# BLE_Reader.net
KiCad netlist of a schematic drawn in Altium Designer
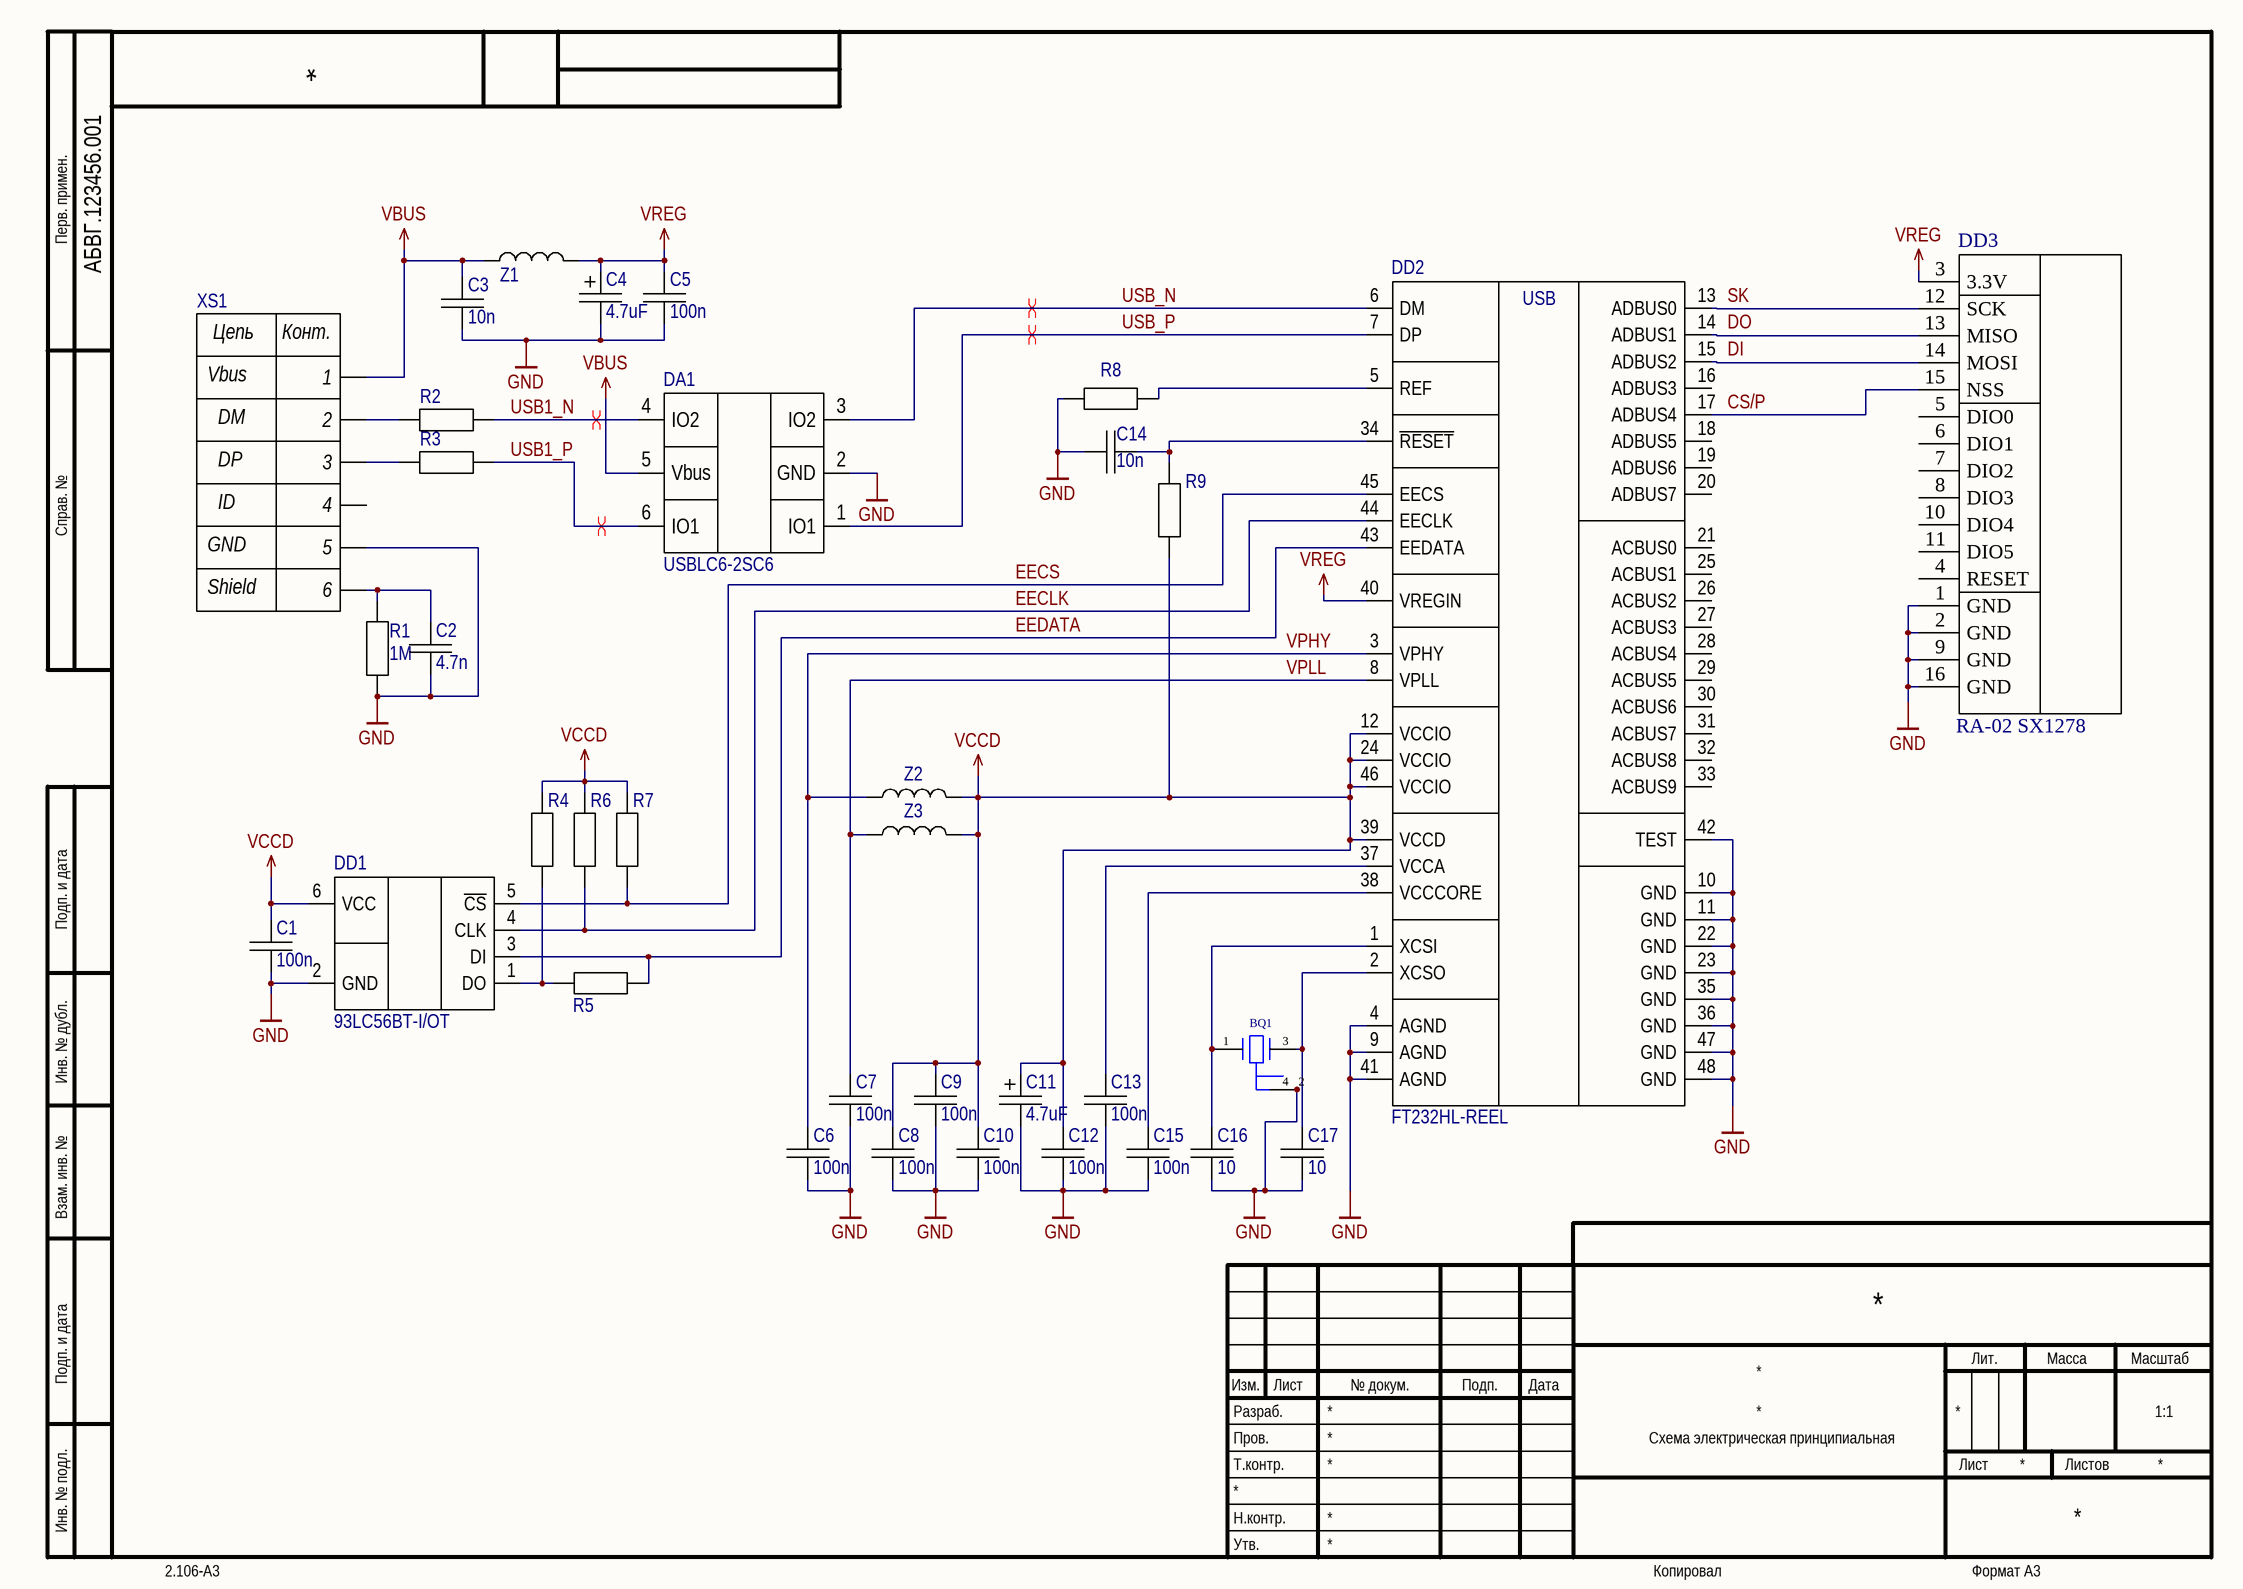
[diagram p0: BLE Reader.SchDoc]

(export (version "E")
  (design (tool "Eeschema 10.0.6"))
  (components
    (comp (ref "BQ1")
      (value "ABM8G-12.000MHZ-4Y-T3")
      (footprint "Abracon_ABM8G_0")
      (libsource (lib "Crys_Abracon_ABM8G-12.000MHZ-4Y-T3_eec") (part "ABM8G-12.000MHZ-4Y-T3"))
    )
    (comp (ref "C1")
      (value "100n")
      (footprint "1608[0603]")
      (description "Конденсатор 1.6x0.8 мм")
      (fields (field (name "TOLERANCE") "±10%"))
      (libsource (lib "RPSLib") (part "CC1608"))
    )
    (comp (ref "C2")
      (value "4.7n")
      (footprint "1608[0603]")
      (description "Конденсатор 1.6x0.8 мм")
      (fields (field (name "TOLERANCE") "±10%"))
      (libsource (lib "RPSLib") (part "CC1608"))
    )
    (comp (ref "C3")
      (value "10n")
      (footprint "1608[0603]")
      (description "Конденсатор 1.6x0.8 мм")
      (fields (field (name "TOLERANCE") "±10%"))
      (libsource (lib "RPSLib") (part "CC1608"))
    )
    (comp (ref "C4")
      (value "4.7uF")
      (footprint "C1206")
      (description "Tantalum Surface Mount Capacitor, Size A")
      (fields (field (name "VOLTAGE") "16"))
      (libsource (lib "RPSLib") (part "CT3216-A"))
    )
    (comp (ref "C5")
      (value "100n")
      (footprint "1608[0603]")
      (description "Конденсатор 1.6x0.8 мм")
      (fields (field (name "TOLERANCE") "±10%"))
      (libsource (lib "RPSLib") (part "CC1608"))
    )
    (comp (ref "C6")
      (value "100n")
      (footprint "1608[0603]")
      (description "Конденсатор 1.6x0.8 мм")
      (fields (field (name "TOLERANCE") "±10%"))
      (libsource (lib "RPSLib") (part "CC1608"))
    )
    (comp (ref "C7")
      (value "100n")
      (footprint "1608[0603]")
      (description "Конденсатор 1.6x0.8 мм")
      (fields (field (name "TOLERANCE") "±10%"))
      (libsource (lib "RPSLib") (part "CC1608"))
    )
    (comp (ref "C8")
      (value "100n")
      (footprint "1608[0603]")
      (description "Конденсатор 1.6x0.8 мм")
      (fields (field (name "TOLERANCE") "±10%"))
      (libsource (lib "RPSLib") (part "CC1608"))
    )
    (comp (ref "C9")
      (value "100n")
      (footprint "1608[0603]")
      (description "Конденсатор 1.6x0.8 мм")
      (fields (field (name "TOLERANCE") "±10%"))
      (libsource (lib "RPSLib") (part "CC1608"))
    )
    (comp (ref "C10")
      (value "100n")
      (footprint "1608[0603]")
      (description "Конденсатор 1.6x0.8 мм")
      (fields (field (name "TOLERANCE") "±10%"))
      (libsource (lib "RPSLib") (part "CC1608"))
    )
    (comp (ref "C11")
      (value "4.7uF")
      (footprint "C1206")
      (description "Tantalum Surface Mount Capacitor, Size A")
      (fields (field (name "VOLTAGE") "16"))
      (libsource (lib "RPSLib") (part "CT3216-A"))
    )
    (comp (ref "C12")
      (value "100n")
      (footprint "1608[0603]")
      (description "Конденсатор 1.6x0.8 мм")
      (fields (field (name "TOLERANCE") "±10%"))
      (libsource (lib "RPSLib") (part "CC1608"))
    )
    (comp (ref "C13")
      (value "100n")
      (footprint "1608[0603]")
      (description "Конденсатор 1.6x0.8 мм")
      (fields (field (name "TOLERANCE") "±10%"))
      (libsource (lib "RPSLib") (part "CC1608"))
    )
    (comp (ref "C14")
      (value "10n")
      (footprint "1608[0603]")
      (description "Конденсатор 1.6x0.8 мм")
      (fields (field (name "TOLERANCE") "±10%"))
      (libsource (lib "RPSLib") (part "CC1608"))
    )
    (comp (ref "C15")
      (value "100n")
      (footprint "1608[0603]")
      (description "Конденсатор 1.6x0.8 мм")
      (fields (field (name "TOLERANCE") "±10%"))
      (libsource (lib "RPSLib") (part "CC1608"))
    )
    (comp (ref "C16")
      (value "10")
      (footprint "1608[0603]")
      (description "Конденсатор 1.6x0.8 мм")
      (fields (field (name "TOLERANCE") "±10%"))
      (libsource (lib "RPSLib") (part "CC1608"))
    )
    (comp (ref "C17")
      (value "10")
      (footprint "1608[0603]")
      (description "Конденсатор 1.6x0.8 мм")
      (fields (field (name "TOLERANCE") "±10%"))
      (libsource (lib "RPSLib") (part "CC1608"))
    )
    (comp (ref "DA1")
      (value "USBLC6-2SC6")
      (footprint "STMicroelectronics_USBLC6-2SC6_0")
      (description "USB protection IC")
      (fields (field (name "MANUFACTURER") "STMicroelectronics"))
      (libsource (lib "RPSLib") (part "USBLC6-2SC6"))
    )
    (comp (ref "DD1")
      (value "93LC56BT-I/OT")
      (footprint "SOT-23-OT6_N")
      (description "IC EEPROM 2K SPI 2MHZ SOT23-6")
      (fields (field (name "MANUFACTURER") "Microchip"))
      (libsource (lib "RPSLib") (part "93LC56BT-I/OT"))
    )
    (comp (ref "DD2")
      (value "FT232HL-REEL")
      (footprint "LQFP-48_L")
      (description "IC HS USB TO UART/FIFO 48LQFP")
      (fields (field (name "MANUFACTURER") "FTDI"))
      (libsource (lib "RPSLib") (part "FT232HL-REEL"))
    )
    (comp (ref "DD3") (value "RA-02 SX1278") (footprint "RA-02") (libsource (lib "RA-02") (part "RA-02")))
    (comp (ref "R1")
      (value "1M")
      (footprint "J1-0603")
      (description "Резистор 1.6x0.8 мм")
      (fields (field (name "TOLERANCE") "±5%") (field (name "MANUFACTURER PART NUMBER") "RC0603JR-071ML"))
      (libsource (lib "RPSLib") (part "R1608"))
    )
    (comp (ref "R2")
      (value "R1608")
      (footprint "J1-0603")
      (description "Резистор 1.6x0.8 мм")
      (fields (field (name "TOLERANCE") "±1%"))
      (libsource (lib "RPSLib") (part "R1608"))
    )
    (comp (ref "R3")
      (value "R1608")
      (footprint "J1-0603")
      (description "Резистор 1.6x0.8 мм")
      (fields (field (name "TOLERANCE") "±1%"))
      (libsource (lib "RPSLib") (part "R1608"))
    )
    (comp (ref "R4")
      (value "R1608")
      (footprint "J1-0603")
      (description "Резистор 1.6x0.8 мм")
      (fields (field (name "TOLERANCE") "±5%"))
      (libsource (lib "RPSLib") (part "R1608"))
    )
    (comp (ref "R5")
      (value "R1608")
      (footprint "J1-0603")
      (description "Резистор 1.6x0.8 мм")
      (fields (field (name "TOLERANCE") "±5%"))
      (libsource (lib "RPSLib") (part "R1608"))
    )
    (comp (ref "R6")
      (value "R1608")
      (footprint "J1-0603")
      (description "Резистор 1.6x0.8 мм")
      (fields (field (name "TOLERANCE") "±5%"))
      (libsource (lib "RPSLib") (part "R1608"))
    )
    (comp (ref "R7")
      (value "R1608")
      (footprint "J1-0603")
      (description "Резистор 1.6x0.8 мм")
      (fields (field (name "TOLERANCE") "±5%"))
      (libsource (lib "RPSLib") (part "R1608"))
    )
    (comp (ref "R8")
      (value "R1608")
      (footprint "J1-0603")
      (description "Резистор 1.6x0.8 мм")
      (fields (field (name "TOLERANCE") "±1%"))
      (libsource (lib "RPSLib") (part "R1608"))
    )
    (comp (ref "R9")
      (value "R1608")
      (footprint "J1-0603")
      (description "Резистор 1.6x0.8 мм")
      (fields (field (name "TOLERANCE") "±5%"))
      (libsource (lib "RPSLib") (part "R1608"))
    )
    (comp (ref "XS1")
      (value "UX60SC-MB-5S8(80)")
      (footprint "UX60SC-MB-5S8(80)")
      (description "USB - mini B USB 2.0 Receptacle Connector 5 Position Surface Mount, Right Angle; Through Hole")
      (fields (field (name "MANUFACTURER") "Hirose"))
      (libsource (lib "RPSLib") (part "UX60SC-MB-5S8(80)"))
    )
    (comp (ref "Z1")
      (value "BLM18AG601SN1D")
      (footprint "INDC1608L")
      (description "FERRITE CHIP 600 OHM 500MA 0603")
      (fields (field (name "MANUFACTURER") "Murata") (field (name "TOLERANCE") "25%"))
      (libsource (lib "RPSLib") (part "BLM18AG601SN1D"))
    )
    (comp (ref "Z2")
      (value "BLM18AG601SN1D")
      (footprint "INDC1608L")
      (description "FERRITE CHIP 600 OHM 500MA 0603")
      (fields (field (name "MANUFACTURER") "Murata") (field (name "TOLERANCE") "25%"))
      (libsource (lib "RPSLib") (part "BLM18AG601SN1D"))
    )
    (comp (ref "Z3")
      (value "BLM18AG601SN1D")
      (footprint "INDC1608L")
      (description "FERRITE CHIP 600 OHM 500MA 0603")
      (fields (field (name "MANUFACTURER") "Murata") (field (name "TOLERANCE") "25%"))
      (libsource (lib "RPSLib") (part "BLM18AG601SN1D"))
    )
  )
  (nets
    (net (code "1") (name "/CS{slash}P") (class "Default")
      (node (ref "DD2") (pin "17") (pinfunction "ADBUS4_17") (pintype "passive"))
      (node (ref "DD3") (pin "15") (pinfunction "NSS_15") (pintype "passive"))
    )
    (net (code "4") (name "/EECLK") (class "Default")
      (node (ref "DD1") (pin "4") (pinfunction "CLK_4") (pintype "passive"))
      (node (ref "DD2") (pin "44") (pinfunction "EECLK_44") (pintype "passive"))
      (node (ref "R6") (pin "1") (pinfunction "1_1") (pintype "passive"))
    )
    (net (code "5") (name "/EECS") (class "Default")
      (node (ref "DD1") (pin "5") (pinfunction "~{CS}_5") (pintype "passive"))
      (node (ref "DD2") (pin "45") (pinfunction "EECS_45") (pintype "passive"))
      (node (ref "R7") (pin "1") (pinfunction "1_1") (pintype "passive"))
    )
    (net (code "6") (name "/EEDATA") (class "Default")
      (node (ref "DD1") (pin "3") (pinfunction "DI_3") (pintype "passive"))
      (node (ref "DD2") (pin "43") (pinfunction "EEDATA_43") (pintype "passive"))
      (node (ref "R5") (pin "1") (pinfunction "1_1") (pintype "passive"))
    )
    (net (code "8") (name "/SK") (class "Default")
      (node (ref "DD2") (pin "13") (pinfunction "ADBUS0_13") (pintype "passive"))
      (node (ref "DD3") (pin "12") (pinfunction "SCK_12") (pintype "passive"))
    )
    (net (code "9") (name "/USB1_N") (class "Default")
      (node (ref "DA1") (pin "4") (pinfunction "IO2_4") (pintype "passive"))
      (node (ref "R2") (pin "1") (pinfunction "1_1") (pintype "passive"))
    )
    (net (code "10") (name "/USB1_P") (class "Default")
      (node (ref "DA1") (pin "6") (pinfunction "IO1_6") (pintype "passive"))
      (node (ref "R3") (pin "1") (pinfunction "1_1") (pintype "passive"))
    )
    (net (code "11") (name "/USB_N") (class "Default")
      (node (ref "DA1") (pin "3") (pinfunction "IO2_3") (pintype "passive"))
      (node (ref "DD2") (pin "6") (pinfunction "DM_6") (pintype "passive"))
    )
    (net (code "12") (name "/USB_P") (class "Default")
      (node (ref "DA1") (pin "1") (pinfunction "IO1_1") (pintype "passive"))
      (node (ref "DD2") (pin "7") (pinfunction "DP_7") (pintype "passive"))
    )
    (net (code "13") (name "/VPHY") (class "Default")
      (node (ref "C6") (pin "2") (pinfunction "2_2") (pintype "passive"))
      (node (ref "DD2") (pin "3") (pinfunction "VPHY_3") (pintype "passive"))
      (node (ref "Z2") (pin "1") (pinfunction "1_1") (pintype "passive"))
    )
    (net (code "14") (name "/VPLL") (class "Default")
      (node (ref "C7") (pin "2") (pinfunction "2_2") (pintype "passive"))
      (node (ref "DD2") (pin "8") (pinfunction "VPLL_8") (pintype "passive"))
      (node (ref "Z3") (pin "1") (pinfunction "1_1") (pintype "passive"))
    )
    (net (code "15") (name "GND") (class "Default")
      (node (ref "BQ1") (pin "2") (pinfunction "GND_2") (pintype "passive"))
      (node (ref "BQ1") (pin "4") (pinfunction "GND_4") (pintype "passive"))
      (node (ref "C1") (pin "1") (pinfunction "1_1") (pintype "passive"))
      (node (ref "C10") (pin "1") (pinfunction "1_1") (pintype "passive"))
      (node (ref "C11") (pin "2") (pinfunction "2_2") (pintype "passive"))
      (node (ref "C12") (pin "1") (pinfunction "1_1") (pintype "passive"))
      (node (ref "C13") (pin "1") (pinfunction "1_1") (pintype "passive"))
      (node (ref "C14") (pin "2") (pinfunction "2_2") (pintype "passive"))
      (node (ref "C15") (pin "1") (pinfunction "1_1") (pintype "passive"))
      (node (ref "C16") (pin "1") (pinfunction "1_1") (pintype "passive"))
      (node (ref "C17") (pin "1") (pinfunction "1_1") (pintype "passive"))
      (node (ref "C2") (pin "1") (pinfunction "1_1") (pintype "passive"))
      (node (ref "C3") (pin "1") (pinfunction "1_1") (pintype "passive"))
      (node (ref "C4") (pin "2") (pinfunction "2_2") (pintype "passive"))
      (node (ref "C5") (pin "1") (pinfunction "1_1") (pintype "passive"))
      (node (ref "C6") (pin "1") (pinfunction "1_1") (pintype "passive"))
      (node (ref "C7") (pin "1") (pinfunction "1_1") (pintype "passive"))
      (node (ref "C8") (pin "1") (pinfunction "1_1") (pintype "passive"))
      (node (ref "C9") (pin "1") (pinfunction "1_1") (pintype "passive"))
      (node (ref "DA1") (pin "2") (pinfunction "GND_2") (pintype "passive"))
      (node (ref "DD1") (pin "2") (pinfunction "GND_2") (pintype "passive"))
      (node (ref "DD2") (pin "10") (pinfunction "GND_10") (pintype "passive"))
      (node (ref "DD2") (pin "11") (pinfunction "GND_11") (pintype "passive"))
      (node (ref "DD2") (pin "22") (pinfunction "GND_22") (pintype "passive"))
      (node (ref "DD2") (pin "23") (pinfunction "GND_23") (pintype "passive"))
      (node (ref "DD2") (pin "35") (pinfunction "GND_35") (pintype "passive"))
      (node (ref "DD2") (pin "36") (pinfunction "GND_36") (pintype "passive"))
      (node (ref "DD2") (pin "4") (pinfunction "AGND_4") (pintype "passive"))
      (node (ref "DD2") (pin "41") (pinfunction "AGND_41") (pintype "passive"))
      (node (ref "DD2") (pin "42") (pinfunction "TEST_42") (pintype "passive"))
      (node (ref "DD2") (pin "47") (pinfunction "GND_47") (pintype "passive"))
      (node (ref "DD2") (pin "48") (pinfunction "GND_48") (pintype "passive"))
      (node (ref "DD2") (pin "9") (pinfunction "AGND_9") (pintype "passive"))
      (node (ref "DD3") (pin "1") (pinfunction "GND_1") (pintype "passive"))
      (node (ref "DD3") (pin "16") (pinfunction "GND_16") (pintype "passive"))
      (node (ref "DD3") (pin "2") (pinfunction "GND_2") (pintype "passive"))
      (node (ref "DD3") (pin "9") (pinfunction "GND_9") (pintype "passive"))
      (node (ref "R1") (pin "2") (pinfunction "2_2") (pintype "passive"))
      (node (ref "R8") (pin "2") (pinfunction "2_2") (pintype "passive"))
      (node (ref "XS1") (pin "5") (pinfunction "5_5") (pintype "passive"))
    )
    (net (code "16") (name "Net-(C2-Pad2)") (class "Default")
      (node (ref "C2") (pin "2") (pinfunction "2_2") (pintype "passive"))
      (node (ref "R1") (pin "1") (pinfunction "1_1") (pintype "passive"))
      (node (ref "XS1") (pin "6") (pinfunction "6_6") (pintype "passive"))
    )
    (net (code "17") (name "Net-(DD1-DO)") (class "Default")
      (node (ref "DD1") (pin "1") (pinfunction "DO_1") (pintype "passive"))
      (node (ref "R4") (pin "1") (pinfunction "1_1") (pintype "passive"))
      (node (ref "R5") (pin "2") (pinfunction "2_2") (pintype "passive"))
    )
    (net (code "18") (name "Net-(DD2-ADBUS1)") (class "Default")
      (node (ref "DD2") (pin "14") (pinfunction "ADBUS1_14") (pintype "passive"))
      (node (ref "DD3") (pin "13") (pinfunction "MISO_13") (pintype "passive"))
    )
    (net (code "19") (name "Net-(DD2-ADBUS2)") (class "Default")
      (node (ref "DD2") (pin "15") (pinfunction "ADBUS2_15") (pintype "passive"))
      (node (ref "DD3") (pin "14") (pinfunction "MOSI_14") (pintype "passive"))
    )
    (net (code "20") (name "Net-(DD2-REF)") (class "Default")
      (node (ref "DD2") (pin "5") (pinfunction "REF_5") (pintype "passive"))
      (node (ref "R8") (pin "1") (pinfunction "1_1") (pintype "passive"))
    )
    (net (code "21") (name "Net-(DD2-VCCA)") (class "Default")
      (node (ref "C13") (pin "2") (pinfunction "2_2") (pintype "passive"))
      (node (ref "DD2") (pin "37") (pinfunction "VCCA_37") (pintype "passive"))
    )
    (net (code "22") (name "Net-(DD2-VCCCORE)") (class "Default")
      (node (ref "C15") (pin "2") (pinfunction "2_2") (pintype "passive"))
      (node (ref "DD2") (pin "38") (pinfunction "VCCCORE_38") (pintype "passive"))
    )
    (net (code "23") (name "Net-(DD2-XCSI)") (class "Default")
      (node (ref "BQ1") (pin "1") (pinfunction "1_1") (pintype "passive"))
      (node (ref "C16") (pin "2") (pinfunction "2_2") (pintype "passive"))
      (node (ref "DD2") (pin "1") (pinfunction "XCSI_1") (pintype "passive"))
    )
    (net (code "24") (name "Net-(DD2-XCSO)") (class "Default")
      (node (ref "BQ1") (pin "3") (pinfunction "3_3") (pintype "passive"))
      (node (ref "C17") (pin "2") (pinfunction "2_2") (pintype "passive"))
      (node (ref "DD2") (pin "2") (pinfunction "XCSO_2") (pintype "passive"))
    )
    (net (code "25") (name "Net-(DD2-~{RESET})") (class "Default")
      (node (ref "C14") (pin "1") (pinfunction "1_1") (pintype "passive"))
      (node (ref "DD2") (pin "34") (pinfunction "~{RESET}_34") (pintype "passive"))
      (node (ref "R9") (pin "2") (pinfunction "2_2") (pintype "passive"))
    )
    (net (code "26") (name "Net-(R2-Pad2)") (class "Default")
      (node (ref "R2") (pin "2") (pinfunction "2_2") (pintype "passive"))
      (node (ref "XS1") (pin "2") (pinfunction "2_2") (pintype "passive"))
    )
    (net (code "27") (name "Net-(R3-Pad2)") (class "Default")
      (node (ref "R3") (pin "2") (pinfunction "2_2") (pintype "passive"))
      (node (ref "XS1") (pin "3") (pinfunction "3_3") (pintype "passive"))
    )
    (net (code "28") (name "VBUS") (class "Default")
      (node (ref "C3") (pin "2") (pinfunction "2_2") (pintype "passive"))
      (node (ref "DA1") (pin "5") (pinfunction "Vbus_5") (pintype "passive"))
      (node (ref "XS1") (pin "1") (pinfunction "1_1") (pintype "passive"))
      (node (ref "Z1") (pin "1") (pinfunction "1_1") (pintype "passive"))
    )
    (net (code "29") (name "VCCD") (class "Default")
      (node (ref "C1") (pin "2") (pinfunction "2_2") (pintype "passive"))
      (node (ref "C10") (pin "2") (pinfunction "2_2") (pintype "passive"))
      (node (ref "C11") (pin "1") (pinfunction "1_1") (pintype "passive"))
      (node (ref "C12") (pin "2") (pinfunction "2_2") (pintype "passive"))
      (node (ref "C8") (pin "2") (pinfunction "2_2") (pintype "passive"))
      (node (ref "C9") (pin "2") (pinfunction "2_2") (pintype "passive"))
      (node (ref "DD1") (pin "6") (pinfunction "VCC_6") (pintype "passive"))
      (node (ref "DD2") (pin "12") (pinfunction "VCCIO_12") (pintype "passive"))
      (node (ref "DD2") (pin "24") (pinfunction "VCCIO_24") (pintype "passive"))
      (node (ref "DD2") (pin "39") (pinfunction "VCCD_39") (pintype "passive"))
      (node (ref "DD2") (pin "46") (pinfunction "VCCIO_46") (pintype "passive"))
      (node (ref "R4") (pin "2") (pinfunction "2_2") (pintype "passive"))
      (node (ref "R6") (pin "2") (pinfunction "2_2") (pintype "passive"))
      (node (ref "R7") (pin "2") (pinfunction "2_2") (pintype "passive"))
      (node (ref "R9") (pin "1") (pinfunction "1_1") (pintype "passive"))
      (node (ref "Z2") (pin "2") (pinfunction "2_2") (pintype "passive"))
      (node (ref "Z3") (pin "2") (pinfunction "2_2") (pintype "passive"))
    )
    (net (code "30") (name "VREG") (class "Default")
      (node (ref "C4") (pin "1") (pinfunction "1_1") (pintype "passive"))
      (node (ref "C5") (pin "2") (pinfunction "2_2") (pintype "passive"))
      (node (ref "DD2") (pin "40") (pinfunction "VREGIN_40") (pintype "passive"))
      (node (ref "DD3") (pin "3") (pinfunction "3.3V_3") (pintype "passive"))
      (node (ref "Z1") (pin "2") (pinfunction "2_2") (pintype "passive"))
    )
    (net (code "31") (name "unconnected-(DD2-ACBUS0-Pad21)") (class "Default")
      (node (ref "DD2") (pin "21") (pinfunction "ACBUS0_21") (pintype "passive"))
    )
    (net (code "32") (name "unconnected-(DD2-ACBUS1-Pad25)") (class "Default")
      (node (ref "DD2") (pin "25") (pinfunction "ACBUS1_25") (pintype "passive"))
    )
    (net (code "33") (name "unconnected-(DD2-ACBUS2-Pad26)") (class "Default")
      (node (ref "DD2") (pin "26") (pinfunction "ACBUS2_26") (pintype "passive"))
    )
    (net (code "34") (name "unconnected-(DD2-ACBUS3-Pad27)") (class "Default")
      (node (ref "DD2") (pin "27") (pinfunction "ACBUS3_27") (pintype "passive"))
    )
    (net (code "35") (name "unconnected-(DD2-ACBUS4-Pad28)") (class "Default")
      (node (ref "DD2") (pin "28") (pinfunction "ACBUS4_28") (pintype "passive"))
    )
    (net (code "36") (name "unconnected-(DD2-ACBUS5-Pad29)") (class "Default")
      (node (ref "DD2") (pin "29") (pinfunction "ACBUS5_29") (pintype "passive"))
    )
    (net (code "37") (name "unconnected-(DD2-ACBUS6-Pad30)") (class "Default")
      (node (ref "DD2") (pin "30") (pinfunction "ACBUS6_30") (pintype "passive"))
    )
    (net (code "38") (name "unconnected-(DD2-ACBUS7-Pad31)") (class "Default")
      (node (ref "DD2") (pin "31") (pinfunction "ACBUS7_31") (pintype "passive"))
    )
    (net (code "39") (name "unconnected-(DD2-ACBUS8-Pad32)") (class "Default")
      (node (ref "DD2") (pin "32") (pinfunction "ACBUS8_32") (pintype "passive"))
    )
    (net (code "40") (name "unconnected-(DD2-ACBUS9-Pad33)") (class "Default")
      (node (ref "DD2") (pin "33") (pinfunction "ACBUS9_33") (pintype "passive"))
    )
    (net (code "41") (name "unconnected-(DD2-ADBUS3-Pad16)") (class "Default")
      (node (ref "DD2") (pin "16") (pinfunction "ADBUS3_16") (pintype "passive"))
    )
    (net (code "42") (name "unconnected-(DD2-ADBUS5-Pad18)") (class "Default")
      (node (ref "DD2") (pin "18") (pinfunction "ADBUS5_18") (pintype "passive"))
    )
    (net (code "43") (name "unconnected-(DD2-ADBUS6-Pad19)") (class "Default")
      (node (ref "DD2") (pin "19") (pinfunction "ADBUS6_19") (pintype "passive"))
    )
    (net (code "44") (name "unconnected-(DD2-ADBUS7-Pad20)") (class "Default")
      (node (ref "DD2") (pin "20") (pinfunction "ADBUS7_20") (pintype "passive"))
    )
    (net (code "45") (name "unconnected-(DD3-DIO0-Pad5)") (class "Default")
      (node (ref "DD3") (pin "5") (pinfunction "DIO0_5") (pintype "passive"))
    )
    (net (code "46") (name "unconnected-(DD3-DIO1-Pad6)") (class "Default")
      (node (ref "DD3") (pin "6") (pinfunction "DIO1_6") (pintype "passive"))
    )
    (net (code "47") (name "unconnected-(DD3-DIO2-Pad7)") (class "Default")
      (node (ref "DD3") (pin "7") (pinfunction "DIO2_7") (pintype "passive"))
    )
    (net (code "48") (name "unconnected-(DD3-DIO3-Pad8)") (class "Default")
      (node (ref "DD3") (pin "8") (pinfunction "DIO3_8") (pintype "passive"))
    )
    (net (code "49") (name "unconnected-(DD3-DIO4-Pad10)") (class "Default")
      (node (ref "DD3") (pin "10") (pinfunction "DIO4_10") (pintype "passive"))
    )
    (net (code "50") (name "unconnected-(DD3-DIO5-Pad11)") (class "Default")
      (node (ref "DD3") (pin "11") (pinfunction "DIO5_11") (pintype "passive"))
    )
    (net (code "51") (name "unconnected-(DD3-RESET-Pad4)") (class "Default")
      (node (ref "DD3") (pin "4") (pinfunction "RESET_4") (pintype "passive"))
    )
    (net (code "52") (name "unconnected-(XS1-Pad4)") (class "Default")
      (node (ref "XS1") (pin "4") (pinfunction "4_4") (pintype "passive"))
    )
  )
)
